# AD9959-DDS_DA_-__2025-04-27_17-19-20.net
KiCad netlist of a schematic drawn in EasyEDA Pro
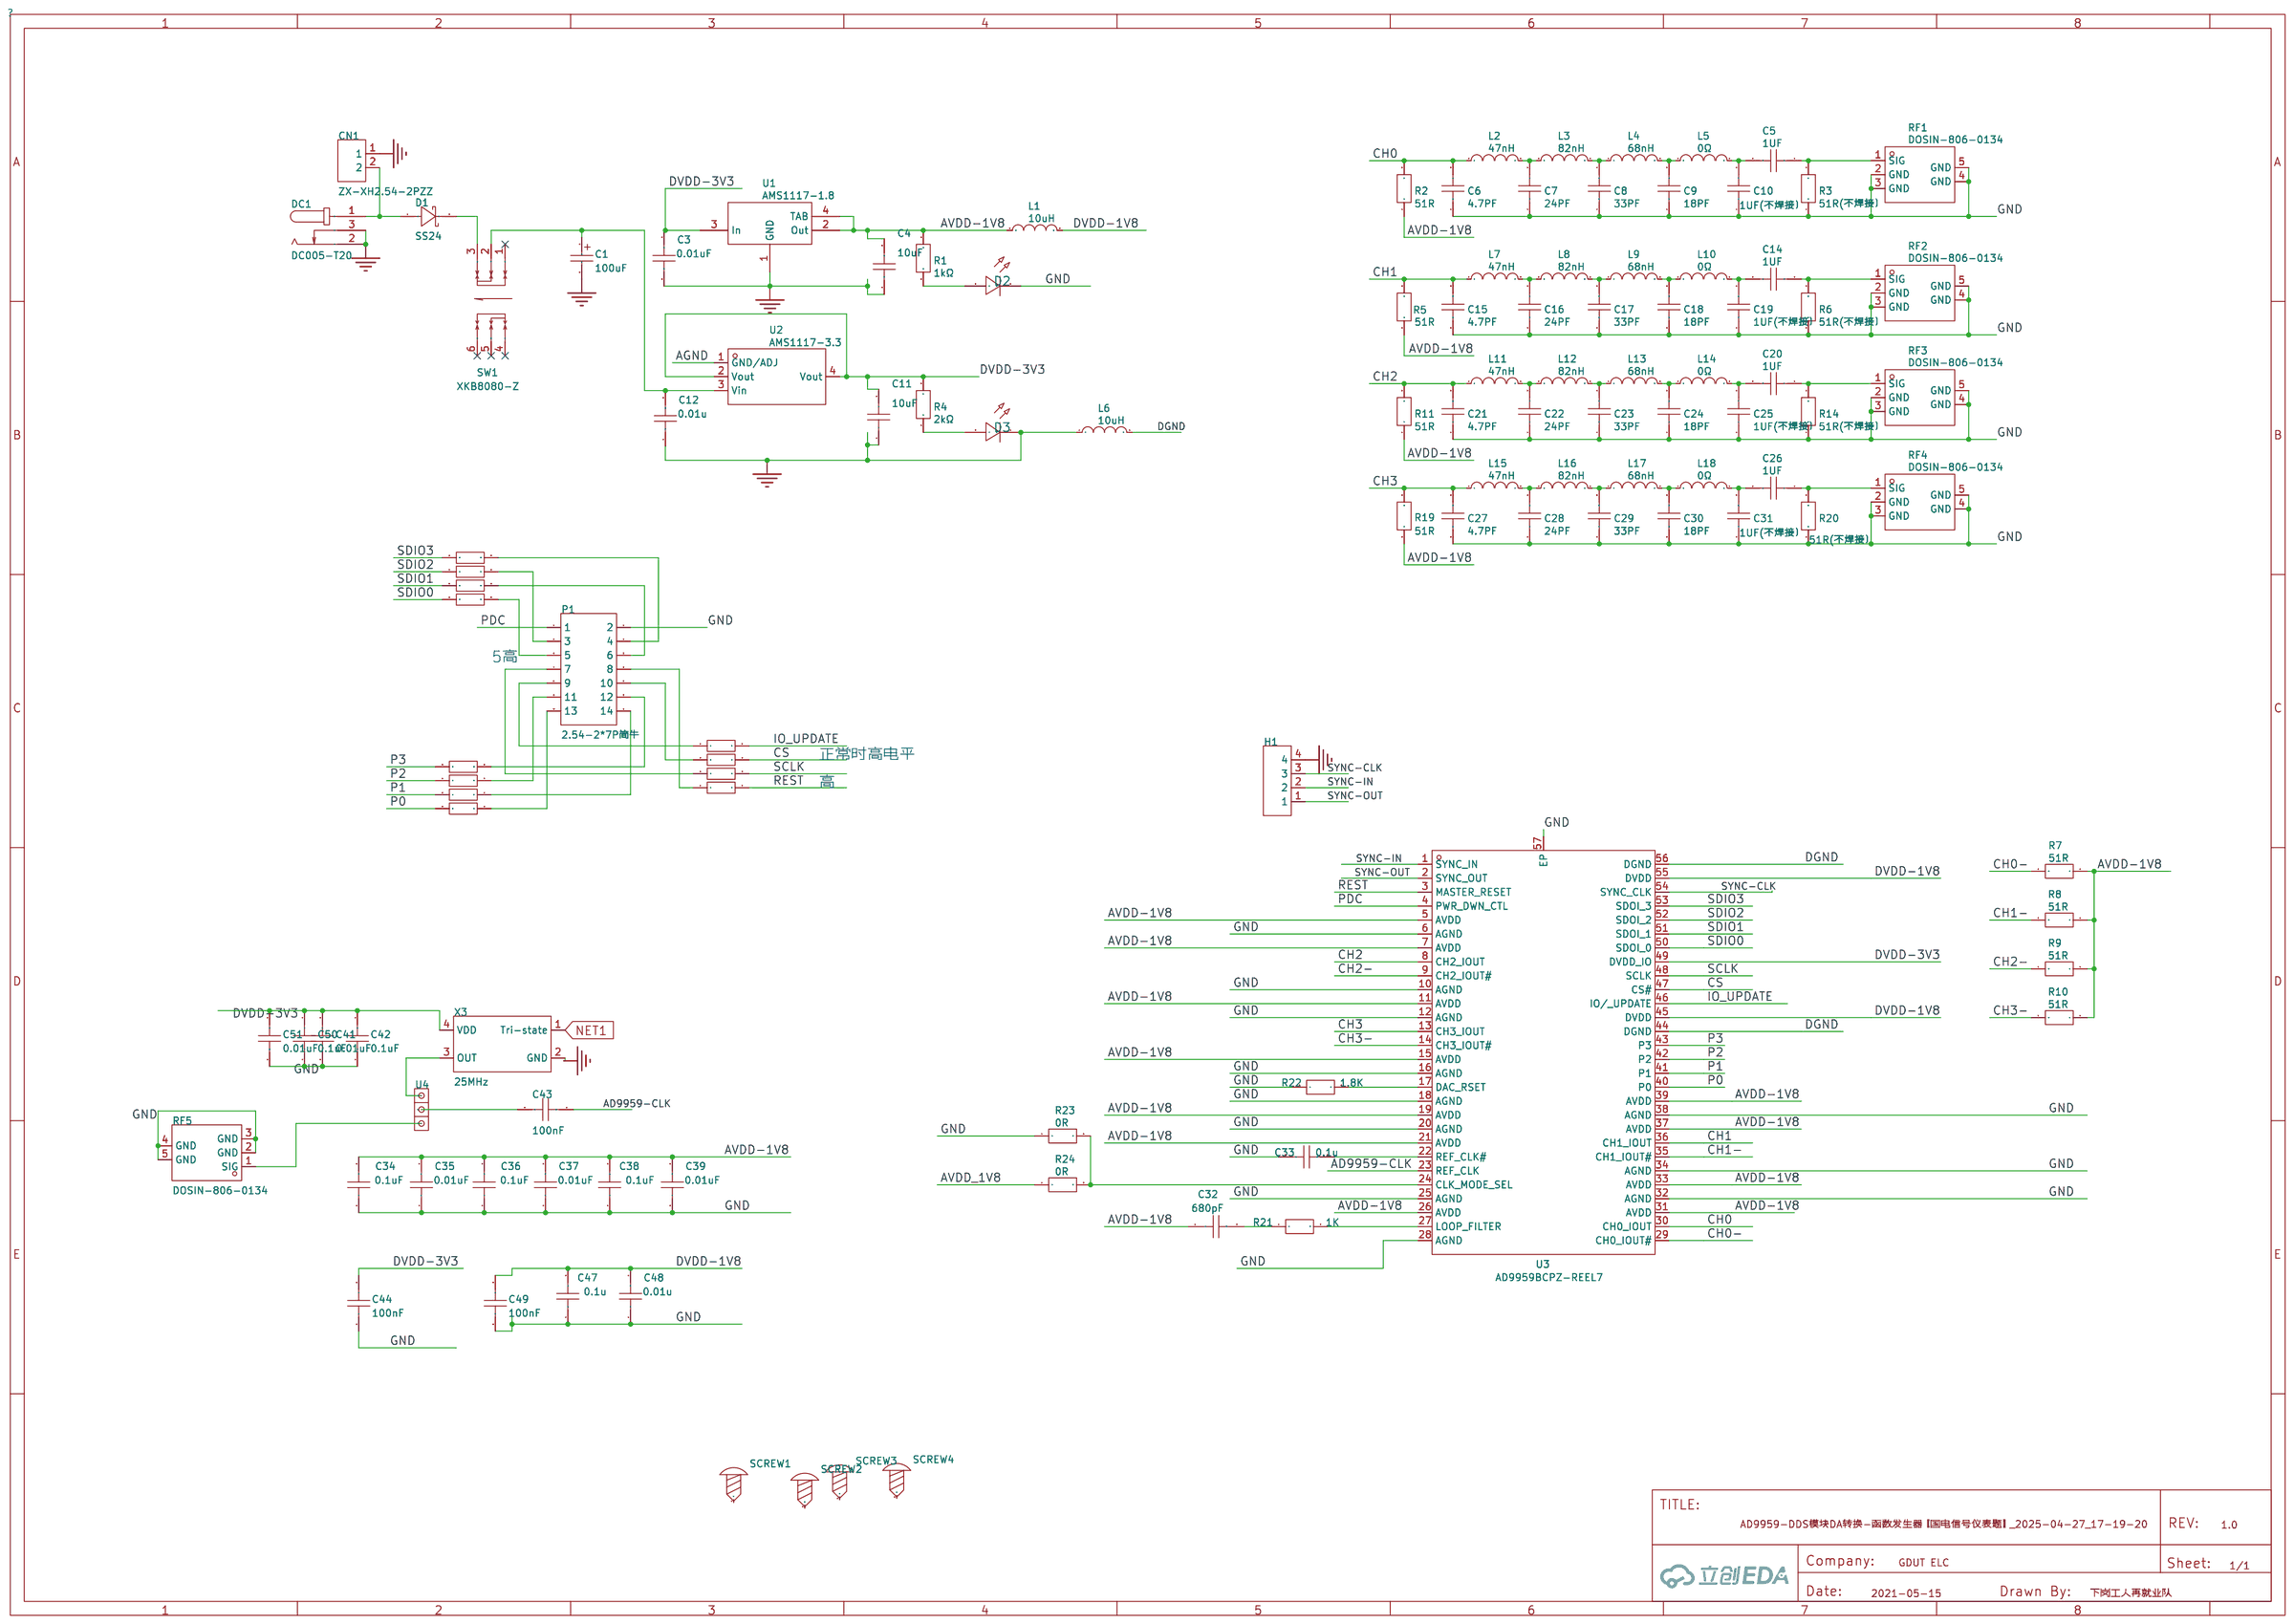
[diagram p0: schematic sheet]

(export (version "E")
  (design (tool "Eeschema 10.0.6"))
  (components
    (comp (ref "C1")
      (value "100uF")
      (footprint "easyedapro:CASE-D_7343")
      (description "容值:100uF;精度:±10%;额定电压:16V;等效串联电阻:600mΩ@100kHz;")
      (fields (field (name "Manufacturer Part") "TAJD107K016RNJ") (field (name "Manufacturer") "Kyocera AVX"))
      (libsource (lib "easyedapro") (part "TAJD107K016RNJ"))
    )
    (comp (ref "C3")
      (value "0.01uF")
      (footprint "easyedapro:footprint_f44b")
      (libsource (lib "easyedapro") (part "0.01uF"))
    )
    (comp (ref "C4")
      (value "10uF")
      (footprint "easyedapro:C1210")
      (description "容值:10uF;精度:±10%;额定电压:50V;材质(温度系数):X7R;")
      (fields
        (field (name "Manufacturer Part") "CL32B106KBJNNNE")
        (field (name "Manufacturer") "SAMSUNG(三星)")
      )
      (libsource (lib "easyedapro") (part "CL32B106KBJNNNE"))
    )
    (comp (ref "C5")
      (value "1UF")
      (footprint "easyedapro:footprint_873f")
      (libsource (lib "easyedapro") (part "1UF"))
    )
    (comp (ref "C6")
      (value "4.7PF")
      (footprint "easyedapro:footprint_873f")
      (libsource (lib "easyedapro") (part "4.7PF"))
    )
    (comp (ref "C7")
      (value "24PF")
      (footprint "easyedapro:footprint_445a")
      (libsource (lib "easyedapro") (part "24PF"))
    )
    (comp (ref "C8")
      (value "33PF")
      (footprint "easyedapro:footprint_445a")
      (libsource (lib "easyedapro") (part "33PF"))
    )
    (comp (ref "C9")
      (value "18PF")
      (footprint "easyedapro:footprint_873f")
      (libsource (lib "easyedapro") (part "18PF"))
    )
    (comp (ref "C10")
      (value "1UF(不焊接）")
      (footprint "easyedapro:footprint_445a")
      (libsource (lib "easyedapro") (part "1UF(不焊接）"))
    )
    (comp (ref "C11")
      (value "10uF")
      (footprint "easyedapro:C1210")
      (description "容值:10uF;精度:±10%;额定电压:50V;材质(温度系数):X7R;")
      (fields
        (field (name "Manufacturer Part") "CL32B106KBJNNNE")
        (field (name "Manufacturer") "SAMSUNG(三星)")
      )
      (libsource (lib "easyedapro") (part "CL32B106KBJNNNE"))
    )
    (comp (ref "C12")
      (value "0.01u")
      (footprint "easyedapro:footprint_f44b")
      (libsource (lib "easyedapro") (part "0.01u"))
    )
    (comp (ref "C14")
      (value "1UF")
      (footprint "easyedapro:footprint_873f")
      (libsource (lib "easyedapro") (part "1UF"))
    )
    (comp (ref "C15")
      (value "4.7PF")
      (footprint "easyedapro:footprint_873f")
      (libsource (lib "easyedapro") (part "4.7PF"))
    )
    (comp (ref "C16")
      (value "24PF")
      (footprint "easyedapro:footprint_445a")
      (libsource (lib "easyedapro") (part "24PF"))
    )
    (comp (ref "C17")
      (value "33PF")
      (footprint "easyedapro:footprint_445a")
      (libsource (lib "easyedapro") (part "33PF"))
    )
    (comp (ref "C18")
      (value "18PF")
      (footprint "easyedapro:footprint_873f")
      (libsource (lib "easyedapro") (part "18PF"))
    )
    (comp (ref "C19")
      (value "1UF(不焊接）")
      (footprint "easyedapro:footprint_445a")
      (libsource (lib "easyedapro") (part "1UF(不焊接）"))
    )
    (comp (ref "C20")
      (value "1UF")
      (footprint "easyedapro:footprint_873f")
      (libsource (lib "easyedapro") (part "1UF"))
    )
    (comp (ref "C21")
      (value "4.7PF")
      (footprint "easyedapro:footprint_873f")
      (libsource (lib "easyedapro") (part "4.7PF"))
    )
    (comp (ref "C22")
      (value "24PF")
      (footprint "easyedapro:footprint_445a")
      (libsource (lib "easyedapro") (part "24PF"))
    )
    (comp (ref "C23")
      (value "33PF")
      (footprint "easyedapro:footprint_445a")
      (libsource (lib "easyedapro") (part "33PF"))
    )
    (comp (ref "C24")
      (value "18PF")
      (footprint "easyedapro:footprint_873f")
      (libsource (lib "easyedapro") (part "18PF"))
    )
    (comp (ref "C25")
      (value "1UF(不焊接）")
      (footprint "easyedapro:footprint_445a")
      (libsource (lib "easyedapro") (part "1UF(不焊接）"))
    )
    (comp (ref "C26")
      (value "1UF")
      (footprint "easyedapro:footprint_873f")
      (libsource (lib "easyedapro") (part "1UF"))
    )
    (comp (ref "C27")
      (value "4.7PF")
      (footprint "easyedapro:footprint_873f")
      (libsource (lib "easyedapro") (part "4.7PF"))
    )
    (comp (ref "C28")
      (value "24PF")
      (footprint "easyedapro:footprint_445a")
      (libsource (lib "easyedapro") (part "24PF"))
    )
    (comp (ref "C29")
      (value "33PF")
      (footprint "easyedapro:footprint_445a")
      (libsource (lib "easyedapro") (part "33PF"))
    )
    (comp (ref "C30")
      (value "18PF")
      (footprint "easyedapro:footprint_873f")
      (libsource (lib "easyedapro") (part "18PF"))
    )
    (comp (ref "C31")
      (value "1UF(不焊接）")
      (footprint "easyedapro:footprint_445a")
      (libsource (lib "easyedapro") (part "1UF(不焊接）"))
    )
    (comp (ref "C32")
      (value "680pF")
      (footprint "easyedapro:footprint_f44b")
      (libsource (lib "easyedapro") (part "680pF"))
    )
    (comp (ref "C33")
      (value "0.1u")
      (footprint "easyedapro:footprint_f44b")
      (libsource (lib "easyedapro") (part "0.1u"))
    )
    (comp (ref "C34")
      (value "0.1uF")
      (footprint "easyedapro:footprint_f44b")
      (libsource (lib "easyedapro") (part "0.1uF"))
    )
    (comp (ref "C35")
      (value "0.01uF")
      (footprint "easyedapro:footprint_f44b")
      (libsource (lib "easyedapro") (part "0.01uF"))
    )
    (comp (ref "C36")
      (value "0.1uF")
      (footprint "easyedapro:footprint_f44b")
      (libsource (lib "easyedapro") (part "0.1uF"))
    )
    (comp (ref "C37")
      (value "0.01uF")
      (footprint "easyedapro:footprint_f44b")
      (libsource (lib "easyedapro") (part "0.01uF"))
    )
    (comp (ref "C38")
      (value "0.1uF")
      (footprint "easyedapro:footprint_f44b")
      (libsource (lib "easyedapro") (part "0.1uF"))
    )
    (comp (ref "C39")
      (value "0.01uF")
      (footprint "easyedapro:footprint_f44b")
      (libsource (lib "easyedapro") (part "0.01uF"))
    )
    (comp (ref "C41")
      (value "0.01uF")
      (footprint "easyedapro:footprint_f44b")
      (libsource (lib "easyedapro") (part "0.01uF"))
    )
    (comp (ref "C42")
      (value "0.1uF")
      (footprint "easyedapro:footprint_f44b")
      (libsource (lib "easyedapro") (part "0.1uF"))
    )
    (comp (ref "C43")
      (value "100nF")
      (footprint "easyedapro:C0603")
      (libsource (lib "easyedapro") (part "CapAcitance"))
    )
    (comp (ref "C44")
      (value "100nF")
      (footprint "easyedapro:C0603")
      (libsource (lib "easyedapro") (part "CapAcitance"))
    )
    (comp (ref "C47")
      (value "0.1u")
      (footprint "easyedapro:footprint_f44b")
      (libsource (lib "easyedapro") (part "0.1u"))
    )
    (comp (ref "C48")
      (value "0.01u")
      (footprint "easyedapro:footprint_f44b")
      (libsource (lib "easyedapro") (part "0.01u"))
    )
    (comp (ref "C49")
      (value "100nF")
      (footprint "easyedapro:C0603")
      (libsource (lib "easyedapro") (part "CapAcitance"))
    )
    (comp (ref "C50")
      (value "0.1uF")
      (footprint "easyedapro:footprint_f44b")
      (libsource (lib "easyedapro") (part "0.1uF"))
    )
    (comp (ref "C51")
      (value "0.01uF")
      (footprint "easyedapro:footprint_f44b")
      (libsource (lib "easyedapro") (part "0.01uF"))
    )
    (comp (ref "CN1")
      (value "ZX-XH2.54-2PZZ")
      (footprint "easyedapro:CONN-TH_2P-P2.50_HX25003-2A")
      (fields (field (name "Manufacturer") "Megastar(兆星)"))
      (libsource (lib "easyedapro") (part "ZX-XH2.54-2PZZ"))
    )
    (comp (ref "D1")
      (value "SS24")
      (footprint "easyedapro:SMA_L4.3-W2.6-LS5.0-FD")
      (description "二极管配置:独立式;正向压降(Vf):550mV@1.0A;直流反向耐压(Vr):40V;整流电流:2A;")
      (fields (field (name "Manufacturer") "宏迦橙"))
      (libsource (lib "easyedapro") (part "SS24_C7420362"))
    )
    (comp (ref "D2")
      (value "~")
      (footprint "easyedapro:LED_0603")
      (libsource (lib "easyedapro") (part "LED_R"))
    )
    (comp (ref "D3")
      (value "~")
      (footprint "easyedapro:LED_0603")
      (libsource (lib "easyedapro") (part "LED_R"))
    )
    (comp (ref "DC1")
      (value "DC005-T20")
      (footprint "easyedapro:DC-IN-TH_DC005-T20")
      (description "连接器类型:DC电源插座;安装方式:弯插;触点内径:2mm;触点外径:6.3mm;额定电流:3A;额定电压:12V;工作温度:-10°C~+60°C;")
      (fields (field (name "Manufacturer") "SOFNG(硕方)"))
      (libsource (lib "easyedapro") (part "DC005-2.0MM"))
    )
    (comp (ref "H1")
      (value "~")
      (footprint "easyedapro:HDR-TH_4P-P2.54-V-M")
      (libsource (lib "easyedapro") (part "PZ254V-11-04P"))
    )
    (comp (ref "L1")
      (value "10uH")
      (footprint "easyedapro:footprint_4fbc")
      (fields (field (name "Manufacturer Part") "LK2125100K-T") (field (name "Manufacturer") "Taiyo Yuden"))
      (libsource (lib "easyedapro") (part "10uH"))
    )
    (comp (ref "L2")
      (value "47nH")
      (footprint "easyedapro:footprint_9e1d")
      (fields (field (name "Manufacturer Part") "SDCL1608C47NJTDF") (field (name "Manufacturer") "Sunlord"))
      (libsource (lib "easyedapro") (part "47nH"))
    )
    (comp (ref "L3")
      (value "82nH")
      (footprint "easyedapro:footprint_9e1d")
      (fields (field (name "Manufacturer Part") "SDCL1608C82NJTDF") (field (name "Manufacturer") "Sunlord"))
      (libsource (lib "easyedapro") (part "82nH"))
    )
    (comp (ref "L4")
      (value "68nH")
      (footprint "easyedapro:footprint_9e1d")
      (fields (field (name "Manufacturer Part") "SDCL1608C68NJTF") (field (name "Manufacturer") "Sunlord"))
      (libsource (lib "easyedapro") (part "68nH"))
    )
    (comp (ref "L5")
      (value "0Ω")
      (footprint "easyedapro:footprint_9e1d")
      (fields (field (name "Manufacturer Part") "CBG160808U000T") (field (name "Manufacturer") "FH"))
      (libsource (lib "easyedapro") (part "0Ω"))
    )
    (comp (ref "L6")
      (value "10uH")
      (footprint "easyedapro:footprint_4fbc")
      (fields (field (name "Manufacturer Part") "LK2125100K-T") (field (name "Manufacturer") "Taiyo Yuden"))
      (libsource (lib "easyedapro") (part "10uH"))
    )
    (comp (ref "L7")
      (value "47nH")
      (footprint "easyedapro:footprint_9e1d")
      (fields (field (name "Manufacturer Part") "SDCL1608C47NJTDF") (field (name "Manufacturer") "Sunlord"))
      (libsource (lib "easyedapro") (part "47nH"))
    )
    (comp (ref "L8")
      (value "82nH")
      (footprint "easyedapro:footprint_9e1d")
      (fields (field (name "Manufacturer Part") "SDCL1608C82NJTDF") (field (name "Manufacturer") "Sunlord"))
      (libsource (lib "easyedapro") (part "82nH"))
    )
    (comp (ref "L9")
      (value "68nH")
      (footprint "easyedapro:footprint_9e1d")
      (fields (field (name "Manufacturer Part") "SDCL1608C68NJTF") (field (name "Manufacturer") "Sunlord"))
      (libsource (lib "easyedapro") (part "68nH"))
    )
    (comp (ref "L10")
      (value "0Ω")
      (footprint "easyedapro:footprint_9e1d")
      (fields (field (name "Manufacturer Part") "CBG160808U000T") (field (name "Manufacturer") "FH"))
      (libsource (lib "easyedapro") (part "0Ω"))
    )
    (comp (ref "L11")
      (value "47nH")
      (footprint "easyedapro:footprint_9e1d")
      (fields (field (name "Manufacturer Part") "SDCL1608C47NJTDF") (field (name "Manufacturer") "Sunlord"))
      (libsource (lib "easyedapro") (part "47nH"))
    )
    (comp (ref "L12")
      (value "82nH")
      (footprint "easyedapro:footprint_9e1d")
      (fields (field (name "Manufacturer Part") "SDCL1608C82NJTDF") (field (name "Manufacturer") "Sunlord"))
      (libsource (lib "easyedapro") (part "82nH"))
    )
    (comp (ref "L13")
      (value "68nH")
      (footprint "easyedapro:footprint_9e1d")
      (fields (field (name "Manufacturer Part") "SDCL1608C68NJTF") (field (name "Manufacturer") "Sunlord"))
      (libsource (lib "easyedapro") (part "68nH"))
    )
    (comp (ref "L14")
      (value "0Ω")
      (footprint "easyedapro:footprint_9e1d")
      (fields (field (name "Manufacturer Part") "CBG160808U000T") (field (name "Manufacturer") "FH"))
      (libsource (lib "easyedapro") (part "0Ω"))
    )
    (comp (ref "L15")
      (value "47nH")
      (footprint "easyedapro:footprint_9e1d")
      (fields (field (name "Manufacturer Part") "SDCL1608C47NJTDF") (field (name "Manufacturer") "Sunlord"))
      (libsource (lib "easyedapro") (part "47nH"))
    )
    (comp (ref "L16")
      (value "82nH")
      (footprint "easyedapro:footprint_9e1d")
      (fields (field (name "Manufacturer Part") "SDCL1608C82NJTDF") (field (name "Manufacturer") "Sunlord"))
      (libsource (lib "easyedapro") (part "82nH"))
    )
    (comp (ref "L17")
      (value "68nH")
      (footprint "easyedapro:footprint_9e1d")
      (fields (field (name "Manufacturer Part") "SDCL1608C68NJTF") (field (name "Manufacturer") "Sunlord"))
      (libsource (lib "easyedapro") (part "68nH"))
    )
    (comp (ref "L18")
      (value "0Ω")
      (footprint "easyedapro:footprint_9e1d")
      (fields (field (name "Manufacturer Part") "CBG160808U000T") (field (name "Manufacturer") "FH"))
      (libsource (lib "easyedapro") (part "0Ω"))
    )
    (comp (ref "P1")
      (value "2.54-2*7P简牛")
      (footprint "easyedapro:IDC-TH_14P-P2.54-V-R2-C7-S2.54")
      (description "连接器类型:简牛座;间距:2.54mm;结构:2x7P;封装形式:直插;行距:2.54mm;排数:2;每排PIN数:7;触头材质:黄铜;触头镀层:金;")
      (fields (field (name "Manufacturer") "BOOMELE(博穆精密)"))
      (libsource (lib "easyedapro") (part "HDR-IDC-2.54-2X7P"))
    )
    (comp (ref "R1")
      (value "1kΩ")
      (footprint "easyedapro:footprint_7a0f")
      (libsource (lib "easyedapro") (part "1kΩ"))
    )
    (comp (ref "R2")
      (value "51R")
      (footprint "easyedapro:footprint_e97b")
      (libsource (lib "easyedapro") (part "51R"))
    )
    (comp (ref "R3")
      (value "51R(不焊接）")
      (footprint "easyedapro:footprint_e97b")
      (libsource (lib "easyedapro") (part "51R(不焊接）"))
    )
    (comp (ref "R4")
      (value "2kΩ")
      (footprint "easyedapro:footprint_7a0f")
      (libsource (lib "easyedapro") (part "2kΩ"))
    )
    (comp (ref "R5")
      (value "51R")
      (footprint "easyedapro:footprint_e97b")
      (libsource (lib "easyedapro") (part "51R"))
    )
    (comp (ref "R6")
      (value "51R(不焊接）")
      (footprint "easyedapro:footprint_e97b")
      (libsource (lib "easyedapro") (part "51R(不焊接）"))
    )
    (comp (ref "R7")
      (value "51R")
      (footprint "easyedapro:footprint_e97b")
      (libsource (lib "easyedapro") (part "51R"))
    )
    (comp (ref "R8")
      (value "51R")
      (footprint "easyedapro:footprint_e97b")
      (libsource (lib "easyedapro") (part "51R"))
    )
    (comp (ref "R9")
      (value "51R")
      (footprint "easyedapro:footprint_e97b")
      (libsource (lib "easyedapro") (part "51R"))
    )
    (comp (ref "R10")
      (value "51R")
      (footprint "easyedapro:footprint_e97b")
      (libsource (lib "easyedapro") (part "51R"))
    )
    (comp (ref "R11")
      (value "51R")
      (footprint "easyedapro:footprint_e97b")
      (libsource (lib "easyedapro") (part "51R"))
    )
    (comp (ref "R14")
      (value "51R(不焊接）")
      (footprint "easyedapro:footprint_e97b")
      (libsource (lib "easyedapro") (part "51R(不焊接）"))
    )
    (comp (ref "R19")
      (value "51R")
      (footprint "easyedapro:footprint_e97b")
      (libsource (lib "easyedapro") (part "51R"))
    )
    (comp (ref "R20")
      (value "51R(不焊接）")
      (footprint "easyedapro:footprint_e97b")
      (libsource (lib "easyedapro") (part "51R(不焊接）"))
    )
    (comp (ref "R21")
      (value "1K")
      (footprint "easyedapro:footprint_7a0f")
      (libsource (lib "easyedapro") (part "680R"))
    )
    (comp (ref "R22")
      (value "1.8K")
      (footprint "easyedapro:footprint_7a0f")
      (libsource (lib "easyedapro") (part "2.0k"))
    )
    (comp (ref "R23")
      (value "0R")
      (footprint "easyedapro:footprint_7a0f")
      (libsource (lib "easyedapro") (part "0R"))
    )
    (comp (ref "R24")
      (value "0R")
      (footprint "easyedapro:footprint_7a0f")
      (libsource (lib "easyedapro") (part "0R"))
    )
    (comp (ref "R25") (value "10K") (footprint "easyedapro:R0603") (libsource (lib "easyedapro") (part "电阻")))
    (comp (ref "R26") (value "10K") (footprint "easyedapro:R0603") (libsource (lib "easyedapro") (part "电阻")))
    (comp (ref "R27") (value "10K") (footprint "easyedapro:R0603") (libsource (lib "easyedapro") (part "电阻")))
    (comp (ref "R28") (value "10K") (footprint "easyedapro:R0603") (libsource (lib "easyedapro") (part "电阻")))
    (comp (ref "R29") (value "10K") (footprint "easyedapro:R0603") (libsource (lib "easyedapro") (part "电阻")))
    (comp (ref "R30") (value "10K") (footprint "easyedapro:R0603") (libsource (lib "easyedapro") (part "电阻")))
    (comp (ref "R31") (value "10K") (footprint "easyedapro:R0603") (libsource (lib "easyedapro") (part "电阻")))
    (comp (ref "R32") (value "10K") (footprint "easyedapro:R0603") (libsource (lib "easyedapro") (part "电阻")))
    (comp (ref "R33") (value "10K") (footprint "easyedapro:R0603") (libsource (lib "easyedapro") (part "电阻")))
    (comp (ref "R34") (value "10K") (footprint "easyedapro:R0603") (libsource (lib "easyedapro") (part "电阻")))
    (comp (ref "R35") (value "10K") (footprint "easyedapro:R0603") (libsource (lib "easyedapro") (part "电阻")))
    (comp (ref "R36") (value "10K") (footprint "easyedapro:R0603") (libsource (lib "easyedapro") (part "电阻")))
    (comp (ref "RF1")
      (value "DOSIN-806-0134")
      (footprint "easyedapro:footprint_bc67")
      (fields (field (name "Manufacturer") "dosinconn(德索五金)"))
      (libsource (lib "easyedapro") (part "DOSIN-806-0134"))
    )
    (comp (ref "RF2")
      (value "DOSIN-806-0134")
      (footprint "easyedapro:footprint_bc67")
      (fields (field (name "Manufacturer") "dosinconn(德索五金)"))
      (libsource (lib "easyedapro") (part "DOSIN-806-0134"))
    )
    (comp (ref "RF3")
      (value "DOSIN-806-0134")
      (footprint "easyedapro:footprint_bc67")
      (fields (field (name "Manufacturer") "dosinconn(德索五金)"))
      (libsource (lib "easyedapro") (part "DOSIN-806-0134"))
    )
    (comp (ref "RF4")
      (value "DOSIN-806-0134")
      (footprint "easyedapro:footprint_bc67")
      (fields (field (name "Manufacturer") "dosinconn(德索五金)"))
      (libsource (lib "easyedapro") (part "DOSIN-806-0134"))
    )
    (comp (ref "RF5")
      (value "DOSIN-806-0134")
      (footprint "easyedapro:footprint_bc67")
      (fields (field (name "Manufacturer") "dosinconn(德索五金)"))
      (libsource (lib "easyedapro") (part "DOSIN-806-0134"))
    )
    (comp (ref "SCREW1")
      (value "~")
      (footprint "easyedapro:M3螺丝")
      (libsource (lib "easyedapro") (part "螺丝孔"))
    )
    (comp (ref "SCREW2")
      (value "~")
      (footprint "easyedapro:M3螺丝")
      (libsource (lib "easyedapro") (part "螺丝孔"))
    )
    (comp (ref "SCREW3")
      (value "~")
      (footprint "easyedapro:M3螺丝")
      (libsource (lib "easyedapro") (part "螺丝孔"))
    )
    (comp (ref "SCREW4")
      (value "~")
      (footprint "easyedapro:M3螺丝")
      (libsource (lib "easyedapro") (part "螺丝孔"))
    )
    (comp (ref "SW1")
      (value "XKB8080-Z")
      (footprint "easyedapro:footprint_acf5")
      (fields (field (name "Manufacturer") "XKB Enterprise"))
      (libsource (lib "easyedapro") (part "XKB8080-Z"))
    )
    (comp (ref "U1")
      (value "AMS1117-1.8")
      (footprint "easyedapro:footprint_4fcc")
      (fields (field (name "Manufacturer") "AMS"))
      (libsource (lib "easyedapro") (part "AMS1117-1.8"))
    )
    (comp (ref "U2")
      (value "AMS1117-3.3")
      (footprint "easyedapro:footprint_1b84")
      (fields (field (name "Manufacturer") "AMS"))
      (libsource (lib "easyedapro") (part "AMS1117-3.3"))
    )
    (comp (ref "U3")
      (value "AD9959BCPZ-REEL7")
      (footprint "easyedapro:footprint_2d52")
      (fields (field (name "Manufacturer") "ADI(亚德诺)/LINEAR"))
      (libsource (lib "easyedapro") (part "AD9959BCPZ-REEL7"))
    )
    (comp (ref "U4") (value "~") (footprint "easyedapro:1*3跳线") (libsource (lib "easyedapro") (part "1*3跳线")))
    (comp (ref "X3")
      (value "25MHz")
      (footprint "easyedapro:OSC-SMD_4P-L5.0-W3.2-BL_A")
      (description "频率:25MHz;常温频差:±10ppm;输出模式:CMOS;工作电压:1.8V~3.3V;频率稳定度:±20ppm;")
      (fields (field (name "Manufacturer Part") "OT503225MJBA4SL") (field (name "Manufacturer") "YXC(扬兴晶振)"))
      (libsource (lib "easyedapro") (part "OT503225MJBA4SL"))
    )
  )
  (nets
    (net (code "1") (name "/AD9959-CLK") (class "Default")
      (node (ref "C43") (pin "2") (pinfunction "2_2") (pintype "input"))
      (node (ref "U3") (pin "23") (pinfunction "REF_CLK_23") (pintype "unspecified"))
    )
    (net (code "2") (name "/AGND") (class "Default")
      (node (ref "U2") (pin "1") (pinfunction "GND/ADJ_1") (pintype "unspecified"))
    )
    (net (code "3") (name "/AVDD-1V8") (class "Default")
      (node (ref "C32") (pin "1") (pinfunction "1_1") (pintype "unspecified"))
      (node (ref "C34") (pin "2") (pinfunction "2_2") (pintype "unspecified"))
      (node (ref "C35") (pin "2") (pinfunction "2_2") (pintype "unspecified"))
      (node (ref "C36") (pin "2") (pinfunction "2_2") (pintype "unspecified"))
      (node (ref "C37") (pin "2") (pinfunction "2_2") (pintype "unspecified"))
      (node (ref "C38") (pin "2") (pinfunction "2_2") (pintype "unspecified"))
      (node (ref "C39") (pin "2") (pinfunction "2_2") (pintype "unspecified"))
      (node (ref "C4") (pin "2") (pinfunction "2_2") (pintype "unspecified"))
      (node (ref "L1") (pin "1") (pinfunction "1_1") (pintype "unspecified"))
      (node (ref "R1") (pin "2") (pinfunction "2_2") (pintype "unspecified"))
      (node (ref "R10") (pin "1") (pinfunction "1_1") (pintype "unspecified"))
      (node (ref "R11") (pin "1") (pinfunction "1_1") (pintype "unspecified"))
      (node (ref "R19") (pin "1") (pinfunction "1_1") (pintype "unspecified"))
      (node (ref "R2") (pin "1") (pinfunction "1_1") (pintype "unspecified"))
      (node (ref "R5") (pin "1") (pinfunction "1_1") (pintype "unspecified"))
      (node (ref "R7") (pin "1") (pinfunction "1_1") (pintype "unspecified"))
      (node (ref "R8") (pin "1") (pinfunction "1_1") (pintype "unspecified"))
      (node (ref "R9") (pin "1") (pinfunction "1_1") (pintype "unspecified"))
      (node (ref "U1") (pin "2") (pinfunction "Out_2") (pintype "unspecified"))
      (node (ref "U1") (pin "4") (pinfunction "TAB_4") (pintype "unspecified"))
      (node (ref "U3") (pin "11") (pinfunction "AVDD_11") (pintype "unspecified"))
      (node (ref "U3") (pin "15") (pinfunction "AVDD_15") (pintype "unspecified"))
      (node (ref "U3") (pin "19") (pinfunction "AVDD_19") (pintype "unspecified"))
      (node (ref "U3") (pin "21") (pinfunction "AVDD_21") (pintype "unspecified"))
      (node (ref "U3") (pin "26") (pinfunction "AVDD_26") (pintype "unspecified"))
      (node (ref "U3") (pin "31") (pinfunction "AVDD_31") (pintype "unspecified"))
      (node (ref "U3") (pin "33") (pinfunction "AVDD_33") (pintype "unspecified"))
      (node (ref "U3") (pin "37") (pinfunction "AVDD_37") (pintype "unspecified"))
      (node (ref "U3") (pin "39") (pinfunction "AVDD_39") (pintype "unspecified"))
      (node (ref "U3") (pin "5") (pinfunction "AVDD_5") (pintype "unspecified"))
      (node (ref "U3") (pin "7") (pinfunction "AVDD_7") (pintype "unspecified"))
    )
    (net (code "4") (name "/AVDD_1V8") (class "Default")
      (node (ref "R24") (pin "1") (pinfunction "1_1") (pintype "unspecified"))
    )
    (net (code "5") (name "/CH0") (class "Default")
      (node (ref "C6") (pin "2") (pinfunction "2_2") (pintype "unspecified"))
      (node (ref "L2") (pin "1") (pinfunction "1_1") (pintype "unspecified"))
      (node (ref "R2") (pin "2") (pinfunction "2_2") (pintype "unspecified"))
      (node (ref "U3") (pin "30") (pinfunction "CH0_IOUT_30") (pintype "unspecified"))
    )
    (net (code "6") (name "/CH0-") (class "Default")
      (node (ref "R7") (pin "2") (pinfunction "2_2") (pintype "unspecified"))
      (node (ref "U3") (pin "29") (pinfunction "CH0_IOUT#_29") (pintype "unspecified"))
    )
    (net (code "7") (name "/CH1") (class "Default")
      (node (ref "C15") (pin "2") (pinfunction "2_2") (pintype "unspecified"))
      (node (ref "L7") (pin "1") (pinfunction "1_1") (pintype "unspecified"))
      (node (ref "R5") (pin "2") (pinfunction "2_2") (pintype "unspecified"))
      (node (ref "U3") (pin "36") (pinfunction "CH1_IOUT_36") (pintype "unspecified"))
    )
    (net (code "8") (name "/CH1-") (class "Default")
      (node (ref "R8") (pin "2") (pinfunction "2_2") (pintype "unspecified"))
      (node (ref "U3") (pin "35") (pinfunction "CH1_IOUT#_35") (pintype "unspecified"))
    )
    (net (code "9") (name "/CH2") (class "Default")
      (node (ref "C21") (pin "2") (pinfunction "2_2") (pintype "unspecified"))
      (node (ref "L11") (pin "1") (pinfunction "1_1") (pintype "unspecified"))
      (node (ref "R11") (pin "2") (pinfunction "2_2") (pintype "unspecified"))
      (node (ref "U3") (pin "8") (pinfunction "CH2_IOUT_8") (pintype "unspecified"))
    )
    (net (code "10") (name "/CH2-") (class "Default")
      (node (ref "R9") (pin "2") (pinfunction "2_2") (pintype "unspecified"))
      (node (ref "U3") (pin "9") (pinfunction "CH2_IOUT#_9") (pintype "unspecified"))
    )
    (net (code "11") (name "/CH3") (class "Default")
      (node (ref "C27") (pin "2") (pinfunction "2_2") (pintype "unspecified"))
      (node (ref "L15") (pin "1") (pinfunction "1_1") (pintype "unspecified"))
      (node (ref "R19") (pin "2") (pinfunction "2_2") (pintype "unspecified"))
      (node (ref "U3") (pin "13") (pinfunction "CH3_IOUT_13") (pintype "unspecified"))
    )
    (net (code "12") (name "/CH3-") (class "Default")
      (node (ref "R10") (pin "2") (pinfunction "2_2") (pintype "unspecified"))
      (node (ref "U3") (pin "14") (pinfunction "CH3_IOUT#_14") (pintype "unspecified"))
    )
    (net (code "13") (name "/CS") (class "Default")
      (node (ref "R34") (pin "2") (pinfunction "2_2") (pintype "input"))
      (node (ref "U3") (pin "47") (pinfunction "CS#_47") (pintype "unspecified"))
    )
    (net (code "14") (name "/DGND") (class "Default")
      (node (ref "L6") (pin "2") (pinfunction "2_2") (pintype "unspecified"))
      (node (ref "U3") (pin "44") (pinfunction "DGND_44") (pintype "unspecified"))
      (node (ref "U3") (pin "56") (pinfunction "DGND_56") (pintype "unspecified"))
    )
    (net (code "15") (name "/DVDD-1V8") (class "Default")
      (node (ref "C47") (pin "2") (pinfunction "2_2") (pintype "unspecified"))
      (node (ref "C48") (pin "2") (pinfunction "2_2") (pintype "unspecified"))
      (node (ref "C49") (pin "2") (pinfunction "2_2") (pintype "input"))
      (node (ref "L1") (pin "2") (pinfunction "2_2") (pintype "unspecified"))
      (node (ref "U3") (pin "45") (pinfunction "DVDD_45") (pintype "unspecified"))
      (node (ref "U3") (pin "55") (pinfunction "DVDD_55") (pintype "unspecified"))
    )
    (net (code "16") (name "/DVDD-3V3") (class "Default")
      (node (ref "C11") (pin "2") (pinfunction "2_2") (pintype "unspecified"))
      (node (ref "C3") (pin "2") (pinfunction "2_2") (pintype "unspecified"))
      (node (ref "C41") (pin "1") (pinfunction "1_1") (pintype "unspecified"))
      (node (ref "C42") (pin "1") (pinfunction "1_1") (pintype "unspecified"))
      (node (ref "C44") (pin "2") (pinfunction "2_2") (pintype "input"))
      (node (ref "C50") (pin "1") (pinfunction "1_1") (pintype "unspecified"))
      (node (ref "C51") (pin "1") (pinfunction "1_1") (pintype "unspecified"))
      (node (ref "R4") (pin "2") (pinfunction "2_2") (pintype "unspecified"))
      (node (ref "U1") (pin "3") (pinfunction "In_3") (pintype "unspecified"))
      (node (ref "U2") (pin "2") (pinfunction "Vout_2") (pintype "unspecified"))
      (node (ref "U2") (pin "4") (pinfunction "Vout_4") (pintype "unspecified"))
      (node (ref "U3") (pin "49") (pinfunction "DVDD_IO_49") (pintype "unspecified"))
      (node (ref "X3") (pin "4") (pinfunction "VDD_4") (pintype "unspecified"))
    )
    (net (code "17") (name "/IO_UPDATE") (class "Default")
      (node (ref "R33") (pin "2") (pinfunction "2_2") (pintype "input"))
      (node (ref "U3") (pin "46") (pinfunction "IO/_UPDATE_46") (pintype "unspecified"))
    )
    (net (code "18") (name "/P0") (class "Default")
      (node (ref "R32") (pin "1") (pinfunction "1_1") (pintype "input"))
      (node (ref "U3") (pin "40") (pinfunction "P0_40") (pintype "unspecified"))
    )
    (net (code "19") (name "/P1") (class "Default")
      (node (ref "R31") (pin "1") (pinfunction "1_1") (pintype "input"))
      (node (ref "U3") (pin "41") (pinfunction "P1_41") (pintype "unspecified"))
    )
    (net (code "20") (name "/P2") (class "Default")
      (node (ref "R30") (pin "1") (pinfunction "1_1") (pintype "input"))
      (node (ref "U3") (pin "42") (pinfunction "P2_42") (pintype "unspecified"))
    )
    (net (code "21") (name "/P3") (class "Default")
      (node (ref "R29") (pin "1") (pinfunction "1_1") (pintype "input"))
      (node (ref "U3") (pin "43") (pinfunction "P3_43") (pintype "unspecified"))
    )
    (net (code "22") (name "/PDC") (class "Default")
      (node (ref "P1") (pin "1") (pinfunction "1_1") (pintype "unspecified"))
      (node (ref "U3") (pin "4") (pinfunction "PWR_DWN_CTL_4") (pintype "unspecified"))
    )
    (net (code "23") (name "/REST") (class "Default")
      (node (ref "R36") (pin "2") (pinfunction "2_2") (pintype "input"))
      (node (ref "U3") (pin "3") (pinfunction "MASTER_RESET_3") (pintype "unspecified"))
    )
    (net (code "24") (name "/SCLK") (class "Default")
      (node (ref "R35") (pin "2") (pinfunction "2_2") (pintype "input"))
      (node (ref "U3") (pin "48") (pinfunction "SCLK_48") (pintype "unspecified"))
    )
    (net (code "25") (name "/SDIO0") (class "Default")
      (node (ref "R28") (pin "1") (pinfunction "1_1") (pintype "input"))
      (node (ref "U3") (pin "50") (pinfunction "SDOI_0_50") (pintype "unspecified"))
    )
    (net (code "26") (name "/SDIO1") (class "Default")
      (node (ref "R27") (pin "1") (pinfunction "1_1") (pintype "input"))
      (node (ref "U3") (pin "51") (pinfunction "SDOI_1_51") (pintype "unspecified"))
    )
    (net (code "27") (name "/SDIO2") (class "Default")
      (node (ref "R26") (pin "1") (pinfunction "1_1") (pintype "input"))
      (node (ref "U3") (pin "52") (pinfunction "SDOI_2_52") (pintype "unspecified"))
    )
    (net (code "28") (name "/SDIO3") (class "Default")
      (node (ref "R25") (pin "1") (pinfunction "1_1") (pintype "input"))
      (node (ref "U3") (pin "53") (pinfunction "SDOI_3_53") (pintype "unspecified"))
    )
    (net (code "29") (name "/SYNC-CLK") (class "Default")
      (node (ref "H1") (pin "3") (pinfunction "3_3") (pintype "unspecified"))
      (node (ref "U3") (pin "54") (pinfunction "SYNC_CLK_54") (pintype "unspecified"))
    )
    (net (code "30") (name "/SYNC-IN") (class "Default")
      (node (ref "H1") (pin "2") (pinfunction "2_2") (pintype "unspecified"))
      (node (ref "U3") (pin "1") (pinfunction "SYNC_IN_1") (pintype "unspecified"))
    )
    (net (code "31") (name "/SYNC-OUT") (class "Default")
      (node (ref "H1") (pin "1") (pinfunction "1_1") (pintype "unspecified"))
      (node (ref "U3") (pin "2") (pinfunction "SYNC_OUT_2") (pintype "unspecified"))
    )
    (net (code "32") (name "GND") (class "Default")
      (node (ref "C1") (pin "2") (pinfunction "2_2") (pintype "input"))
      (node (ref "C10") (pin "1") (pinfunction "1_1") (pintype "unspecified"))
      (node (ref "C11") (pin "1") (pinfunction "1_1") (pintype "unspecified"))
      (node (ref "C12") (pin "1") (pinfunction "1_1") (pintype "unspecified"))
      (node (ref "C15") (pin "1") (pinfunction "1_1") (pintype "unspecified"))
      (node (ref "C16") (pin "1") (pinfunction "1_1") (pintype "unspecified"))
      (node (ref "C17") (pin "1") (pinfunction "1_1") (pintype "unspecified"))
      (node (ref "C18") (pin "1") (pinfunction "1_1") (pintype "unspecified"))
      (node (ref "C19") (pin "1") (pinfunction "1_1") (pintype "unspecified"))
      (node (ref "C21") (pin "1") (pinfunction "1_1") (pintype "unspecified"))
      (node (ref "C22") (pin "1") (pinfunction "1_1") (pintype "unspecified"))
      (node (ref "C23") (pin "1") (pinfunction "1_1") (pintype "unspecified"))
      (node (ref "C24") (pin "1") (pinfunction "1_1") (pintype "unspecified"))
      (node (ref "C25") (pin "1") (pinfunction "1_1") (pintype "unspecified"))
      (node (ref "C27") (pin "1") (pinfunction "1_1") (pintype "unspecified"))
      (node (ref "C28") (pin "1") (pinfunction "1_1") (pintype "unspecified"))
      (node (ref "C29") (pin "1") (pinfunction "1_1") (pintype "unspecified"))
      (node (ref "C3") (pin "1") (pinfunction "1_1") (pintype "unspecified"))
      (node (ref "C30") (pin "1") (pinfunction "1_1") (pintype "unspecified"))
      (node (ref "C31") (pin "1") (pinfunction "1_1") (pintype "unspecified"))
      (node (ref "C33") (pin "1") (pinfunction "1_1") (pintype "unspecified"))
      (node (ref "C34") (pin "1") (pinfunction "1_1") (pintype "unspecified"))
      (node (ref "C35") (pin "1") (pinfunction "1_1") (pintype "unspecified"))
      (node (ref "C36") (pin "1") (pinfunction "1_1") (pintype "unspecified"))
      (node (ref "C37") (pin "1") (pinfunction "1_1") (pintype "unspecified"))
      (node (ref "C38") (pin "1") (pinfunction "1_1") (pintype "unspecified"))
      (node (ref "C39") (pin "1") (pinfunction "1_1") (pintype "unspecified"))
      (node (ref "C4") (pin "1") (pinfunction "1_1") (pintype "unspecified"))
      (node (ref "C41") (pin "2") (pinfunction "2_2") (pintype "unspecified"))
      (node (ref "C42") (pin "2") (pinfunction "2_2") (pintype "unspecified"))
      (node (ref "C44") (pin "1") (pinfunction "1_1") (pintype "input"))
      (node (ref "C47") (pin "1") (pinfunction "1_1") (pintype "unspecified"))
      (node (ref "C48") (pin "1") (pinfunction "1_1") (pintype "unspecified"))
      (node (ref "C49") (pin "1") (pinfunction "1_1") (pintype "input"))
      (node (ref "C50") (pin "2") (pinfunction "2_2") (pintype "unspecified"))
      (node (ref "C51") (pin "2") (pinfunction "2_2") (pintype "unspecified"))
      (node (ref "C6") (pin "1") (pinfunction "1_1") (pintype "unspecified"))
      (node (ref "C7") (pin "1") (pinfunction "1_1") (pintype "unspecified"))
      (node (ref "C8") (pin "1") (pinfunction "1_1") (pintype "unspecified"))
      (node (ref "C9") (pin "1") (pinfunction "1_1") (pintype "unspecified"))
      (node (ref "CN1") (pin "1") (pinfunction "1_1") (pintype "unspecified"))
      (node (ref "D2") (pin "1") (pinfunction "C_1") (pintype "input"))
      (node (ref "D3") (pin "1") (pinfunction "C_1") (pintype "input"))
      (node (ref "DC1") (pin "2") (pinfunction "2_2") (pintype "unspecified"))
      (node (ref "DC1") (pin "3") (pinfunction "3_3") (pintype "unspecified"))
      (node (ref "H1") (pin "4") (pinfunction "4_4") (pintype "unspecified"))
      (node (ref "L6") (pin "1") (pinfunction "1_1") (pintype "unspecified"))
      (node (ref "P1") (pin "2") (pinfunction "2_2") (pintype "unspecified"))
      (node (ref "R14") (pin "1") (pinfunction "1_1") (pintype "unspecified"))
      (node (ref "R20") (pin "1") (pinfunction "1_1") (pintype "unspecified"))
      (node (ref "R22") (pin "1") (pinfunction "1_1") (pintype "unspecified"))
      (node (ref "R23") (pin "1") (pinfunction "1_1") (pintype "unspecified"))
      (node (ref "R3") (pin "1") (pinfunction "1_1") (pintype "unspecified"))
      (node (ref "R6") (pin "1") (pinfunction "1_1") (pintype "unspecified"))
      (node (ref "RF1") (pin "2") (pinfunction "GND_2") (pintype "unspecified"))
      (node (ref "RF1") (pin "3") (pinfunction "GND_3") (pintype "unspecified"))
      (node (ref "RF1") (pin "4") (pinfunction "GND_4") (pintype "unspecified"))
      (node (ref "RF1") (pin "5") (pinfunction "GND_5") (pintype "unspecified"))
      (node (ref "RF2") (pin "2") (pinfunction "GND_2") (pintype "unspecified"))
      (node (ref "RF2") (pin "3") (pinfunction "GND_3") (pintype "unspecified"))
      (node (ref "RF2") (pin "4") (pinfunction "GND_4") (pintype "unspecified"))
      (node (ref "RF2") (pin "5") (pinfunction "GND_5") (pintype "unspecified"))
      (node (ref "RF3") (pin "2") (pinfunction "GND_2") (pintype "unspecified"))
      (node (ref "RF3") (pin "3") (pinfunction "GND_3") (pintype "unspecified"))
      (node (ref "RF3") (pin "4") (pinfunction "GND_4") (pintype "unspecified"))
      (node (ref "RF3") (pin "5") (pinfunction "GND_5") (pintype "unspecified"))
      (node (ref "RF4") (pin "2") (pinfunction "GND_2") (pintype "unspecified"))
      (node (ref "RF4") (pin "3") (pinfunction "GND_3") (pintype "unspecified"))
      (node (ref "RF4") (pin "4") (pinfunction "GND_4") (pintype "unspecified"))
      (node (ref "RF4") (pin "5") (pinfunction "GND_5") (pintype "unspecified"))
      (node (ref "RF5") (pin "2") (pinfunction "GND_2") (pintype "unspecified"))
      (node (ref "RF5") (pin "3") (pinfunction "GND_3") (pintype "unspecified"))
      (node (ref "RF5") (pin "4") (pinfunction "GND_4") (pintype "unspecified"))
      (node (ref "RF5") (pin "5") (pinfunction "GND_5") (pintype "unspecified"))
      (node (ref "U1") (pin "1") (pinfunction "GND_1") (pintype "unspecified"))
      (node (ref "U3") (pin "10") (pinfunction "AGND_10") (pintype "unspecified"))
      (node (ref "U3") (pin "12") (pinfunction "AGND_12") (pintype "unspecified"))
      (node (ref "U3") (pin "16") (pinfunction "AGND_16") (pintype "unspecified"))
      (node (ref "U3") (pin "18") (pinfunction "AGND_18") (pintype "unspecified"))
      (node (ref "U3") (pin "20") (pinfunction "AGND_20") (pintype "unspecified"))
      (node (ref "U3") (pin "25") (pinfunction "AGND_25") (pintype "unspecified"))
      (node (ref "U3") (pin "28") (pinfunction "AGND_28") (pintype "unspecified"))
      (node (ref "U3") (pin "32") (pinfunction "AGND_32") (pintype "unspecified"))
      (node (ref "U3") (pin "34") (pinfunction "AGND_34") (pintype "unspecified"))
      (node (ref "U3") (pin "38") (pinfunction "AGND_38") (pintype "unspecified"))
      (node (ref "U3") (pin "57") (pinfunction "EP_57") (pintype "unspecified"))
      (node (ref "U3") (pin "6") (pinfunction "AGND_6") (pintype "unspecified"))
      (node (ref "X3") (pin "2") (pinfunction "GND_2") (pintype "unspecified"))
    )
    (net (code "33") (name "NET1") (class "Default")
      (node (ref "X3") (pin "1") (pinfunction "Tri-state_1") (pintype "unspecified"))
    )
    (net (code "34") (name "Net-(C7-Pad2)") (class "Default")
      (node (ref "C7") (pin "2") (pinfunction "2_2") (pintype "unspecified"))
      (node (ref "L2") (pin "2") (pinfunction "2_2") (pintype "unspecified"))
      (node (ref "L3") (pin "1") (pinfunction "1_1") (pintype "unspecified"))
    )
    (net (code "35") (name "Net-(C8-Pad2)") (class "Default")
      (node (ref "C8") (pin "2") (pinfunction "2_2") (pintype "unspecified"))
      (node (ref "L3") (pin "2") (pinfunction "2_2") (pintype "unspecified"))
      (node (ref "L4") (pin "1") (pinfunction "1_1") (pintype "unspecified"))
    )
    (net (code "36") (name "Net-(C9-Pad2)") (class "Default")
      (node (ref "C9") (pin "2") (pinfunction "2_2") (pintype "unspecified"))
      (node (ref "L4") (pin "2") (pinfunction "2_2") (pintype "unspecified"))
      (node (ref "L5") (pin "1") (pinfunction "1_1") (pintype "unspecified"))
    )
    (net (code "37") (name "Net-(C10-Pad2)") (class "Default")
      (node (ref "C10") (pin "2") (pinfunction "2_2") (pintype "unspecified"))
      (node (ref "C5") (pin "2") (pinfunction "2_2") (pintype "unspecified"))
      (node (ref "L5") (pin "2") (pinfunction "2_2") (pintype "unspecified"))
    )
    (net (code "38") (name "Net-(C14-Pad2)") (class "Default")
      (node (ref "C14") (pin "2") (pinfunction "2_2") (pintype "unspecified"))
      (node (ref "C19") (pin "2") (pinfunction "2_2") (pintype "unspecified"))
      (node (ref "L10") (pin "2") (pinfunction "2_2") (pintype "unspecified"))
    )
    (net (code "39") (name "Net-(C16-Pad2)") (class "Default")
      (node (ref "C16") (pin "2") (pinfunction "2_2") (pintype "unspecified"))
      (node (ref "L7") (pin "2") (pinfunction "2_2") (pintype "unspecified"))
      (node (ref "L8") (pin "1") (pinfunction "1_1") (pintype "unspecified"))
    )
    (net (code "40") (name "Net-(C17-Pad2)") (class "Default")
      (node (ref "C17") (pin "2") (pinfunction "2_2") (pintype "unspecified"))
      (node (ref "L8") (pin "2") (pinfunction "2_2") (pintype "unspecified"))
      (node (ref "L9") (pin "1") (pinfunction "1_1") (pintype "unspecified"))
    )
    (net (code "41") (name "Net-(C18-Pad2)") (class "Default")
      (node (ref "C18") (pin "2") (pinfunction "2_2") (pintype "unspecified"))
      (node (ref "L10") (pin "1") (pinfunction "1_1") (pintype "unspecified"))
      (node (ref "L9") (pin "2") (pinfunction "2_2") (pintype "unspecified"))
    )
    (net (code "42") (name "Net-(C20-Pad2)") (class "Default")
      (node (ref "C20") (pin "2") (pinfunction "2_2") (pintype "unspecified"))
      (node (ref "C25") (pin "2") (pinfunction "2_2") (pintype "unspecified"))
      (node (ref "L14") (pin "2") (pinfunction "2_2") (pintype "unspecified"))
    )
    (net (code "43") (name "Net-(C22-Pad2)") (class "Default")
      (node (ref "C22") (pin "2") (pinfunction "2_2") (pintype "unspecified"))
      (node (ref "L11") (pin "2") (pinfunction "2_2") (pintype "unspecified"))
      (node (ref "L12") (pin "1") (pinfunction "1_1") (pintype "unspecified"))
    )
    (net (code "44") (name "Net-(C23-Pad2)") (class "Default")
      (node (ref "C23") (pin "2") (pinfunction "2_2") (pintype "unspecified"))
      (node (ref "L12") (pin "2") (pinfunction "2_2") (pintype "unspecified"))
      (node (ref "L13") (pin "1") (pinfunction "1_1") (pintype "unspecified"))
    )
    (net (code "45") (name "Net-(C24-Pad2)") (class "Default")
      (node (ref "C24") (pin "2") (pinfunction "2_2") (pintype "unspecified"))
      (node (ref "L13") (pin "2") (pinfunction "2_2") (pintype "unspecified"))
      (node (ref "L14") (pin "1") (pinfunction "1_1") (pintype "unspecified"))
    )
    (net (code "46") (name "Net-(C26-Pad2)") (class "Default")
      (node (ref "C26") (pin "2") (pinfunction "2_2") (pintype "unspecified"))
      (node (ref "C31") (pin "2") (pinfunction "2_2") (pintype "unspecified"))
      (node (ref "L18") (pin "2") (pinfunction "2_2") (pintype "unspecified"))
    )
    (net (code "47") (name "Net-(C28-Pad2)") (class "Default")
      (node (ref "C28") (pin "2") (pinfunction "2_2") (pintype "unspecified"))
      (node (ref "L15") (pin "2") (pinfunction "2_2") (pintype "unspecified"))
      (node (ref "L16") (pin "1") (pinfunction "1_1") (pintype "unspecified"))
    )
    (net (code "48") (name "Net-(C29-Pad2)") (class "Default")
      (node (ref "C29") (pin "2") (pinfunction "2_2") (pintype "unspecified"))
      (node (ref "L16") (pin "2") (pinfunction "2_2") (pintype "unspecified"))
      (node (ref "L17") (pin "1") (pinfunction "1_1") (pintype "unspecified"))
    )
    (net (code "49") (name "Net-(C30-Pad2)") (class "Default")
      (node (ref "C30") (pin "2") (pinfunction "2_2") (pintype "unspecified"))
      (node (ref "L17") (pin "2") (pinfunction "2_2") (pintype "unspecified"))
      (node (ref "L18") (pin "1") (pinfunction "1_1") (pintype "unspecified"))
    )
    (net (code "50") (name "Net-(C32-Pad2)") (class "Default")
      (node (ref "C32") (pin "2") (pinfunction "2_2") (pintype "unspecified"))
      (node (ref "R21") (pin "1") (pinfunction "1_1") (pintype "unspecified"))
    )
    (net (code "51") (name "Net-(C43-Pad1)") (class "Default")
      (node (ref "C43") (pin "1") (pinfunction "1_1") (pintype "input"))
      (node (ref "U4") (pin "2") (pinfunction "2_2") (pintype "input"))
    )
    (net (code "52") (name "Net-(D1-A)") (class "Default")
      (node (ref "CN1") (pin "2") (pinfunction "2_2") (pintype "unspecified"))
      (node (ref "D1") (pin "1") (pinfunction "A_1") (pintype "unspecified"))
      (node (ref "DC1") (pin "1") (pinfunction "1_1") (pintype "unspecified"))
    )
    (net (code "53") (name "Net-(D1-K)") (class "Default")
      (node (ref "D1") (pin "2") (pinfunction "K_2") (pintype "unspecified"))
      (node (ref "SW1") (pin "3") (pinfunction "3_3") (pintype "unspecified"))
    )
    (net (code "54") (name "Net-(D2-A)") (class "Default")
      (node (ref "D2") (pin "2") (pinfunction "A_2") (pintype "input"))
      (node (ref "R1") (pin "1") (pinfunction "1_1") (pintype "unspecified"))
    )
    (net (code "55") (name "Net-(D3-A)") (class "Default")
      (node (ref "D3") (pin "2") (pinfunction "A_2") (pintype "input"))
      (node (ref "R4") (pin "1") (pinfunction "1_1") (pintype "unspecified"))
    )
    (net (code "56") (name "Net-(P1-Pad3)") (class "Default")
      (node (ref "P1") (pin "3") (pinfunction "3_3") (pintype "unspecified"))
      (node (ref "R26") (pin "2") (pinfunction "2_2") (pintype "input"))
    )
    (net (code "57") (name "Net-(P1-Pad4)") (class "Default")
      (node (ref "P1") (pin "4") (pinfunction "4_4") (pintype "unspecified"))
      (node (ref "R25") (pin "2") (pinfunction "2_2") (pintype "input"))
    )
    (net (code "58") (name "Net-(P1-Pad5)") (class "Default")
      (node (ref "P1") (pin "5") (pinfunction "5_5") (pintype "unspecified"))
      (node (ref "R28") (pin "2") (pinfunction "2_2") (pintype "input"))
    )
    (net (code "59") (name "Net-(P1-Pad6)") (class "Default")
      (node (ref "P1") (pin "6") (pinfunction "6_6") (pintype "unspecified"))
      (node (ref "R27") (pin "2") (pinfunction "2_2") (pintype "input"))
    )
    (net (code "60") (name "Net-(P1-Pad7)") (class "Default")
      (node (ref "P1") (pin "7") (pinfunction "7_7") (pintype "unspecified"))
      (node (ref "R35") (pin "1") (pinfunction "1_1") (pintype "input"))
    )
    (net (code "61") (name "Net-(P1-Pad8)") (class "Default")
      (node (ref "P1") (pin "8") (pinfunction "8_8") (pintype "unspecified"))
      (node (ref "R36") (pin "1") (pinfunction "1_1") (pintype "input"))
    )
    (net (code "62") (name "Net-(P1-Pad9)") (class "Default")
      (node (ref "P1") (pin "9") (pinfunction "9_9") (pintype "unspecified"))
      (node (ref "R33") (pin "1") (pinfunction "1_1") (pintype "input"))
    )
    (net (code "63") (name "Net-(P1-Pad10)") (class "Default")
      (node (ref "P1") (pin "10") (pinfunction "10_10") (pintype "unspecified"))
      (node (ref "R34") (pin "1") (pinfunction "1_1") (pintype "input"))
    )
    (net (code "64") (name "Net-(P1-Pad11)") (class "Default")
      (node (ref "P1") (pin "11") (pinfunction "11_11") (pintype "unspecified"))
      (node (ref "R30") (pin "2") (pinfunction "2_2") (pintype "input"))
    )
    (net (code "65") (name "Net-(P1-Pad12)") (class "Default")
      (node (ref "P1") (pin "12") (pinfunction "12_12") (pintype "unspecified"))
      (node (ref "R29") (pin "2") (pinfunction "2_2") (pintype "input"))
    )
    (net (code "66") (name "Net-(P1-Pad13)") (class "Default")
      (node (ref "P1") (pin "13") (pinfunction "13_13") (pintype "unspecified"))
      (node (ref "R32") (pin "2") (pinfunction "2_2") (pintype "input"))
    )
    (net (code "67") (name "Net-(P1-Pad14)") (class "Default")
      (node (ref "P1") (pin "14") (pinfunction "14_14") (pintype "unspecified"))
      (node (ref "R31") (pin "2") (pinfunction "2_2") (pintype "input"))
    )
    (net (code "68") (name "Net-(RF1-SIG)") (class "Default")
      (node (ref "C5") (pin "1") (pinfunction "1_1") (pintype "unspecified"))
      (node (ref "R3") (pin "2") (pinfunction "2_2") (pintype "unspecified"))
      (node (ref "RF1") (pin "1") (pinfunction "SIG_1") (pintype "unspecified"))
    )
    (net (code "69") (name "Net-(RF2-SIG)") (class "Default")
      (node (ref "C14") (pin "1") (pinfunction "1_1") (pintype "unspecified"))
      (node (ref "R6") (pin "2") (pinfunction "2_2") (pintype "unspecified"))
      (node (ref "RF2") (pin "1") (pinfunction "SIG_1") (pintype "unspecified"))
    )
    (net (code "70") (name "Net-(RF3-SIG)") (class "Default")
      (node (ref "C20") (pin "1") (pinfunction "1_1") (pintype "unspecified"))
      (node (ref "R14") (pin "2") (pinfunction "2_2") (pintype "unspecified"))
      (node (ref "RF3") (pin "1") (pinfunction "SIG_1") (pintype "unspecified"))
    )
    (net (code "71") (name "Net-(RF4-SIG)") (class "Default")
      (node (ref "C26") (pin "1") (pinfunction "1_1") (pintype "unspecified"))
      (node (ref "R20") (pin "2") (pinfunction "2_2") (pintype "unspecified"))
      (node (ref "RF4") (pin "1") (pinfunction "SIG_1") (pintype "unspecified"))
    )
    (net (code "72") (name "Net-(RF5-SIG)") (class "Default")
      (node (ref "RF5") (pin "1") (pinfunction "SIG_1") (pintype "unspecified"))
      (node (ref "U4") (pin "1") (pinfunction "1_1") (pintype "input"))
    )
    (net (code "73") (name "Net-(U2-Vin)") (class "Default")
      (node (ref "C1") (pin "1") (pinfunction "1_1") (pintype "input"))
      (node (ref "C12") (pin "2") (pinfunction "2_2") (pintype "unspecified"))
      (node (ref "SW1") (pin "2") (pinfunction "2_2") (pintype "unspecified"))
      (node (ref "U2") (pin "3") (pinfunction "Vin_3") (pintype "unspecified"))
    )
    (net (code "74") (name "Net-(U3-CLK_MODE_SEL)") (class "Default")
      (node (ref "R23") (pin "2") (pinfunction "2_2") (pintype "unspecified"))
      (node (ref "R24") (pin "2") (pinfunction "2_2") (pintype "unspecified"))
      (node (ref "U3") (pin "24") (pinfunction "CLK_MODE_SEL_24") (pintype "unspecified"))
    )
    (net (code "75") (name "Net-(U3-DAC_RSET)") (class "Default")
      (node (ref "R22") (pin "2") (pinfunction "2_2") (pintype "unspecified"))
      (node (ref "U3") (pin "17") (pinfunction "DAC_RSET_17") (pintype "unspecified"))
    )
    (net (code "76") (name "Net-(U3-LOOP_FILTER)") (class "Default")
      (node (ref "R21") (pin "2") (pinfunction "2_2") (pintype "unspecified"))
      (node (ref "U3") (pin "27") (pinfunction "LOOP_FILTER_27") (pintype "unspecified"))
    )
    (net (code "77") (name "Net-(U3-REF_CLK#)") (class "Default")
      (node (ref "C33") (pin "2") (pinfunction "2_2") (pintype "unspecified"))
      (node (ref "U3") (pin "22") (pinfunction "REF_CLK#_22") (pintype "unspecified"))
    )
    (net (code "78") (name "Net-(X3-OUT)") (class "Default")
      (node (ref "U4") (pin "3") (pinfunction "3_3") (pintype "input"))
      (node (ref "X3") (pin "3") (pinfunction "OUT_3") (pintype "unspecified"))
    )
    (net (code "79") (name "unconnected-(SCREW1-Pad1)") (class "Default")
      (node (ref "SCREW1") (pin "1") (pinfunction "1_1") (pintype "input"))
    )
    (net (code "80") (name "unconnected-(SCREW2-Pad1)") (class "Default")
      (node (ref "SCREW2") (pin "1") (pinfunction "1_1") (pintype "input"))
    )
    (net (code "81") (name "unconnected-(SCREW3-Pad1)") (class "Default")
      (node (ref "SCREW3") (pin "1") (pinfunction "1_1") (pintype "input"))
    )
    (net (code "82") (name "unconnected-(SCREW4-Pad1)") (class "Default")
      (node (ref "SCREW4") (pin "1") (pinfunction "1_1") (pintype "input"))
    )
    (net (code "83") (name "unconnected-(SW1-Pad1)") (class "Default")
      (node (ref "SW1") (pin "1") (pinfunction "1_1") (pintype "unspecified+no_connect"))
    )
    (net (code "84") (name "unconnected-(SW1-Pad4)") (class "Default")
      (node (ref "SW1") (pin "4") (pinfunction "4_4") (pintype "unspecified+no_connect"))
    )
    (net (code "85") (name "unconnected-(SW1-Pad5)") (class "Default")
      (node (ref "SW1") (pin "5") (pinfunction "5_5") (pintype "unspecified+no_connect"))
    )
    (net (code "86") (name "unconnected-(SW1-Pad6)") (class "Default")
      (node (ref "SW1") (pin "6") (pinfunction "6_6") (pintype "unspecified+no_connect"))
    )
  )
)
